# bga_test.net
KiCad netlist of a schematic drawn in EAGLE
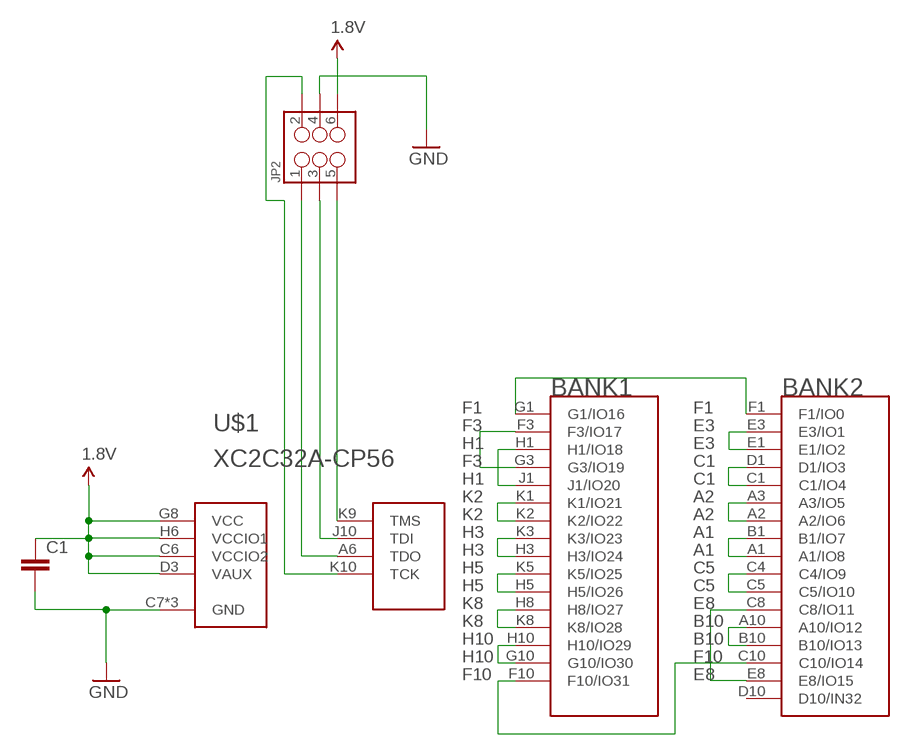
[diagram p0: schematic, sheet 1]

(export (version "E")
  (design (tool "Eeschema 10.0.6"))
  (components
    (comp (ref "C1")
      (value "CAP0402-CAP")
      (footprint "eagle-import:0402-CAP")
      (libsource (lib "eagle-import") (part "CAP0402-CAP"))
    )
    (comp (ref "JP2")
      (value "M03X2NO_SILK")
      (footprint "eagle-import:2X3-NS")
      (libsource (lib "eagle-import") (part "M03X2NO_SILK"))
    )
    (comp (ref "U$1")
      (value "XC2C32A-CP56")
      (footprint "eagle-import:XILINX_CP56")
      (libsource (lib "eagle-import") (part "XC2C32A-CP56"))
    )
  )
  (nets
    (net (code "1") (name "/A1") (class "Default")
      (node (ref "U$1") (pin "A1") (pinfunction "A1/IO8_A1") (pintype "bidirectional"))
      (node (ref "U$1") (pin "B1") (pinfunction "B1/IO7_B1") (pintype "bidirectional"))
    )
    (net (code "2") (name "/A2") (class "Default")
      (node (ref "U$1") (pin "A2") (pinfunction "A2/IO6_A2") (pintype "bidirectional"))
      (node (ref "U$1") (pin "A3") (pinfunction "A3/IO5_A3") (pintype "bidirectional"))
    )
    (net (code "3") (name "/B10") (class "Default")
      (node (ref "U$1") (pin "A10") (pinfunction "A10/IO12_A10") (pintype "bidirectional"))
      (node (ref "U$1") (pin "B10") (pinfunction "B10/IO13_B10") (pintype "bidirectional"))
    )
    (net (code "4") (name "/C1") (class "Default")
      (node (ref "U$1") (pin "C1") (pinfunction "C1/IO4_C1") (pintype "bidirectional"))
      (node (ref "U$1") (pin "D1") (pinfunction "D1/IO3_D1") (pintype "bidirectional"))
    )
    (net (code "5") (name "/C5") (class "Default")
      (node (ref "U$1") (pin "C4") (pinfunction "C4/IO9_C4") (pintype "bidirectional"))
      (node (ref "U$1") (pin "C5") (pinfunction "C5/IO10_C5") (pintype "bidirectional"))
    )
    (net (code "6") (name "/E3") (class "Default")
      (node (ref "U$1") (pin "E1") (pinfunction "E1/IO2_E1") (pintype "bidirectional"))
      (node (ref "U$1") (pin "E3") (pinfunction "E3/IO1_E3") (pintype "bidirectional"))
    )
    (net (code "7") (name "/E8") (class "Default")
      (node (ref "U$1") (pin "C8") (pinfunction "C8/IO11_C8") (pintype "bidirectional"))
      (node (ref "U$1") (pin "E8") (pinfunction "E8/IO15_E8") (pintype "bidirectional"))
    )
    (net (code "8") (name "/F1") (class "Default")
      (node (ref "U$1") (pin "F1") (pinfunction "F1/IO0_F1") (pintype "bidirectional"))
      (node (ref "U$1") (pin "G1") (pinfunction "G1/IO16_G1") (pintype "bidirectional"))
    )
    (net (code "9") (name "/F3") (class "Default")
      (node (ref "U$1") (pin "F3") (pinfunction "F3/IO17_F3") (pintype "bidirectional"))
      (node (ref "U$1") (pin "G3") (pinfunction "G3/IO19_G3") (pintype "bidirectional"))
    )
    (net (code "10") (name "/F10") (class "Default")
      (node (ref "U$1") (pin "C10") (pinfunction "C10/IO14_C10") (pintype "bidirectional"))
      (node (ref "U$1") (pin "F10") (pinfunction "F10/IO31_F10") (pintype "bidirectional"))
    )
    (net (code "11") (name "/H1") (class "Default")
      (node (ref "U$1") (pin "H1") (pinfunction "H1/IO18_H1") (pintype "bidirectional"))
      (node (ref "U$1") (pin "J1") (pinfunction "J1/IO20_J1") (pintype "bidirectional"))
    )
    (net (code "12") (name "/H3") (class "Default")
      (node (ref "U$1") (pin "H3") (pinfunction "H3/IO24_H3") (pintype "bidirectional"))
      (node (ref "U$1") (pin "K3") (pinfunction "K3/IO23_K3") (pintype "bidirectional"))
    )
    (net (code "13") (name "/H5") (class "Default")
      (node (ref "U$1") (pin "H5") (pinfunction "H5/IO26_H5") (pintype "bidirectional"))
      (node (ref "U$1") (pin "K5") (pinfunction "K5/IO25_K5") (pintype "bidirectional"))
    )
    (net (code "14") (name "/H10") (class "Default")
      (node (ref "U$1") (pin "G10") (pinfunction "G10/IO30_G10") (pintype "bidirectional"))
      (node (ref "U$1") (pin "H10") (pinfunction "H10/IO29_H10") (pintype "bidirectional"))
    )
    (net (code "15") (name "/K2") (class "Default")
      (node (ref "U$1") (pin "K1") (pinfunction "K1/IO21_K1") (pintype "bidirectional"))
      (node (ref "U$1") (pin "K2") (pinfunction "K2/IO22_K2") (pintype "bidirectional"))
    )
    (net (code "16") (name "/K8") (class "Default")
      (node (ref "U$1") (pin "H8") (pinfunction "H8/IO27_H8") (pintype "bidirectional"))
      (node (ref "U$1") (pin "K8") (pinfunction "K8/IO28_K8") (pintype "bidirectional"))
    )
    (net (code "17") (name "1.8V") (class "Default")
      (node (ref "C1") (pin "1") (pinfunction "1_1") (pintype "passive"))
      (node (ref "JP2") (pin "6") (pinfunction "6_6") (pintype "bidirectional"))
      (node (ref "U$1") (pin "C6") (pinfunction "VCCIO2_C6") (pintype "bidirectional"))
      (node (ref "U$1") (pin "D3") (pinfunction "VAUX_D3") (pintype "bidirectional"))
      (node (ref "U$1") (pin "G8") (pinfunction "VCC_G8") (pintype "bidirectional"))
      (node (ref "U$1") (pin "H6") (pinfunction "VCCIO1_H6") (pintype "bidirectional"))
    )
    (net (code "18") (name "GND") (class "Default")
      (node (ref "C1") (pin "2") (pinfunction "2_2") (pintype "passive"))
      (node (ref "JP2") (pin "4") (pinfunction "4_4") (pintype "bidirectional"))
      (node (ref "U$1") (pin "C7") (pinfunction "GND_C7") (pintype "bidirectional"))
      (node (ref "U$1") (pin "F8") (pinfunction "GND_F8") (pintype "bidirectional"))
      (node (ref "U$1") (pin "H4") (pinfunction "GND_H4") (pintype "bidirectional"))
    )
    (net (code "19") (name "Net-(U$1A-TCK)") (class "Default")
      (node (ref "JP2") (pin "2") (pinfunction "2_2") (pintype "bidirectional"))
      (node (ref "U$1") (pin "K10") (pinfunction "TCK_K10") (pintype "bidirectional"))
    )
    (net (code "20") (name "Net-(U$1A-TDI)") (class "Default")
      (node (ref "JP2") (pin "3") (pinfunction "3_3") (pintype "bidirectional"))
      (node (ref "U$1") (pin "J10") (pinfunction "TDI_J10") (pintype "bidirectional"))
    )
    (net (code "21") (name "Net-(U$1A-TDO)") (class "Default")
      (node (ref "JP2") (pin "1") (pinfunction "1_1") (pintype "bidirectional"))
      (node (ref "U$1") (pin "A6") (pinfunction "TDO_A6") (pintype "bidirectional"))
    )
    (net (code "22") (name "Net-(U$1A-TMS)") (class "Default")
      (node (ref "JP2") (pin "5") (pinfunction "5_5") (pintype "bidirectional"))
      (node (ref "U$1") (pin "K9") (pinfunction "TMS_K9") (pintype "bidirectional"))
    )
    (net (code "23") (name "unconnected-(U$1A-D10{slash}IN32-PadD10)") (class "Default")
      (node (ref "U$1") (pin "D10") (pinfunction "D10/IN32_D10") (pintype "bidirectional"))
    )
  )
)
